# 01.net
KiCad netlist of a schematic drawn in Altium Designer
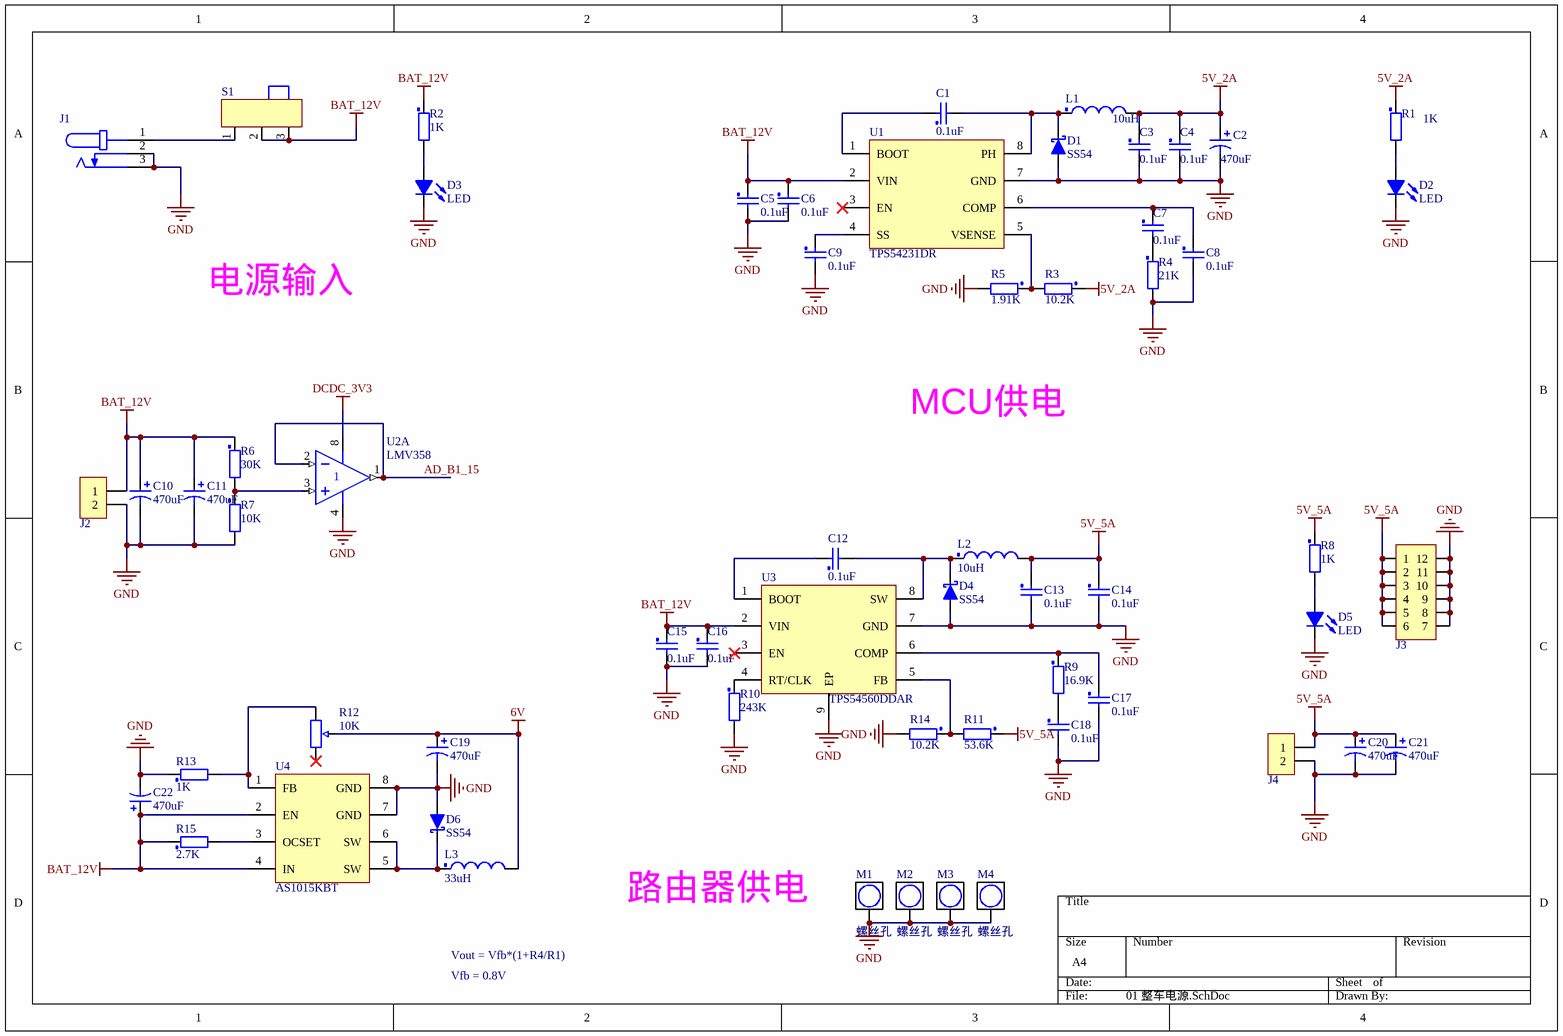
[diagram p0: 01 整车电源.SchDoc]

(export (version "E")
  (design (tool "Eeschema 10.0.6"))
  (components
    (comp (ref "C1")
      (value "0.1uF")
      (footprint "cap0603")
      (description "贴片电容")
      (fields (field (name "PUBLISHER") "Altium Limited"))
      (libsource (lib "元件库") (part "Cap"))
    )
    (comp (ref "C2")
      (value "470uF")
      (footprint "Cap8x10.5mm")
      (description "贴片电解电容 8*10.5mm")
      (fields (field (name "PUBLISHER") "Altium Limited"))
      (libsource (lib "元件库") (part "Cap Pol"))
    )
    (comp (ref "C3")
      (value "0.1uF")
      (footprint "cap0603")
      (description "贴片电容")
      (fields (field (name "PUBLISHER") "Altium Limited"))
      (libsource (lib "元件库") (part "Cap"))
    )
    (comp (ref "C4")
      (value "0.1uF")
      (footprint "cap0603")
      (description "贴片电容")
      (fields (field (name "PUBLISHER") "Altium Limited"))
      (libsource (lib "元件库") (part "Cap"))
    )
    (comp (ref "C5")
      (value "0.1uF")
      (footprint "cap0603")
      (description "贴片电容")
      (fields (field (name "PUBLISHER") "Altium Limited"))
      (libsource (lib "元件库") (part "Cap"))
    )
    (comp (ref "C6")
      (value "0.1uF")
      (footprint "cap0603")
      (description "贴片电容")
      (fields (field (name "PUBLISHER") "Altium Limited"))
      (libsource (lib "元件库") (part "Cap"))
    )
    (comp (ref "C7")
      (value "0.1uF")
      (footprint "cap0603")
      (description "贴片电容")
      (fields (field (name "PUBLISHER") "Altium Limited"))
      (libsource (lib "元件库") (part "Cap"))
    )
    (comp (ref "C8")
      (value "0.1uF")
      (footprint "cap0603")
      (description "贴片电容")
      (fields (field (name "PUBLISHER") "Altium Limited"))
      (libsource (lib "元件库") (part "Cap"))
    )
    (comp (ref "C9")
      (value "0.1uF")
      (footprint "cap0603")
      (description "贴片电容")
      (fields (field (name "PUBLISHER") "Altium Limited"))
      (libsource (lib "元件库") (part "Cap"))
    )
    (comp (ref "C10")
      (value "470uF")
      (footprint "Cap8x10.5mm")
      (description "贴片电解电容 8*10.5mm")
      (fields (field (name "PUBLISHER") "Altium Limited"))
      (libsource (lib "元件库") (part "Cap Pol"))
    )
    (comp (ref "C11")
      (value "470uF")
      (footprint "Cap8x10.5mm")
      (description "贴片电解电容 8*10.5mm")
      (fields (field (name "PUBLISHER") "Altium Limited"))
      (libsource (lib "元件库") (part "Cap Pol"))
    )
    (comp (ref "C12")
      (value "0.1uF")
      (footprint "cap0603")
      (description "贴片电容")
      (fields (field (name "PUBLISHER") "Altium Limited"))
      (libsource (lib "元件库") (part "Cap"))
    )
    (comp (ref "C13")
      (value "0.1uF")
      (footprint "cap0603")
      (description "贴片电容")
      (fields (field (name "PUBLISHER") "Altium Limited"))
      (libsource (lib "元件库") (part "Cap"))
    )
    (comp (ref "C14")
      (value "0.1uF")
      (footprint "cap0603")
      (description "贴片电容")
      (fields (field (name "PUBLISHER") "Altium Limited"))
      (libsource (lib "元件库") (part "Cap"))
    )
    (comp (ref "C15")
      (value "0.1uF")
      (footprint "cap0603")
      (description "贴片电容")
      (fields (field (name "PUBLISHER") "Altium Limited"))
      (libsource (lib "元件库") (part "Cap"))
    )
    (comp (ref "C16")
      (value "0.1uF")
      (footprint "cap0603")
      (description "贴片电容")
      (fields (field (name "PUBLISHER") "Altium Limited"))
      (libsource (lib "元件库") (part "Cap"))
    )
    (comp (ref "C17")
      (value "0.1uF")
      (footprint "cap0603")
      (description "贴片电容")
      (fields (field (name "PUBLISHER") "Altium Limited"))
      (libsource (lib "元件库") (part "Cap"))
    )
    (comp (ref "C18")
      (value "0.1uF")
      (footprint "cap0603")
      (description "贴片电容")
      (fields (field (name "PUBLISHER") "Altium Limited"))
      (libsource (lib "元件库") (part "Cap"))
    )
    (comp (ref "C19")
      (value "470uF")
      (footprint "Cap8x10.5mm")
      (description "贴片电解电容 8*10.5mm")
      (fields (field (name "PUBLISHER") "Altium Limited"))
      (libsource (lib "元件库") (part "Cap Pol"))
    )
    (comp (ref "C20")
      (value "470uF")
      (footprint "Cap8x10.5mm")
      (description "贴片电解电容 8*10.5mm")
      (fields (field (name "PUBLISHER") "Altium Limited"))
      (libsource (lib "元件库") (part "Cap Pol"))
    )
    (comp (ref "C21")
      (value "470uF")
      (footprint "Cap8x10.5mm")
      (description "贴片电解电容 8*10.5mm")
      (fields (field (name "PUBLISHER") "Altium Limited"))
      (libsource (lib "元件库") (part "Cap Pol"))
    )
    (comp (ref "C22")
      (value "470uF")
      (footprint "Cap8x10.5mm")
      (description "贴片电解电容 8*10.5mm")
      (fields (field (name "PUBLISHER") "Altium Limited"))
      (libsource (lib "元件库") (part "Cap Pol"))
    )
    (comp (ref "D1")
      (value "SS54")
      (footprint "SMA(DO-214AC)")
      (description "肖特基二极管")
      (fields (field (name "PUBLISHER") "Altium Limited"))
      (libsource (lib "元件库") (part "D Schottky"))
    )
    (comp (ref "D2")
      (value "LED")
      (footprint "LED")
      (description "贴片LED")
      (fields (field (name "PUBLISHER") "Altium Limited"))
      (libsource (lib "元件库") (part "LED"))
    )
    (comp (ref "D3")
      (value "LED")
      (footprint "LED")
      (description "贴片LED")
      (fields (field (name "PUBLISHER") "Altium Limited"))
      (libsource (lib "元件库") (part "LED"))
    )
    (comp (ref "D4")
      (value "SS54")
      (footprint "SMA(DO-214AC)")
      (description "肖特基二极管")
      (fields (field (name "PUBLISHER") "Altium Limited"))
      (libsource (lib "元件库") (part "D Schottky"))
    )
    (comp (ref "D5")
      (value "LED")
      (footprint "LED")
      (description "贴片LED")
      (fields (field (name "PUBLISHER") "Altium Limited"))
      (libsource (lib "元件库") (part "LED"))
    )
    (comp (ref "D6")
      (value "SS54")
      (footprint "SMA(DO-214AC)")
      (description "肖特基二极管")
      (fields (field (name "PUBLISHER") "Altium Limited"))
      (libsource (lib "元件库") (part "D Schottky"))
    )
    (comp (ref "J1")
      (value "DC输入插座")
      (footprint "DC_IN")
      (description "型号DC-005  外径5.5内径2.1 立创编号C136744")
      (libsource (lib "元件库") (part "DC输入插座"))
    )
    (comp (ref "J2")
      (value "接插件1")
      (footprint "5.08_2p")
      (description "5.08mm拔插式阶段端子，弯针")
      (fields (field (name "版权归属") "源创客"))
      (libsource (lib "元件库") (part "Header 2"))
    )
    (comp (ref "J3")
      (value "2x6")
      (footprint "2*8")
      (description "2.54mm公排针")
      (fields (field (name "版权归属") "源创客"))
      (libsource (lib "元件库") (part "Header 6x2"))
    )
    (comp (ref "J4")
      (value "接插件1")
      (footprint "5.08_2p")
      (description "5.08mm拔插式阶段端子，弯针")
      (fields (field (name "版权归属") "源创客"))
      (libsource (lib "元件库") (part "Header 2"))
    )
    (comp (ref "L1")
      (value "10uH")
      (footprint "CD43")
      (description "贴片功率电感")
      (fields (field (name "PUBLISHER") "Altium Limited"))
      (libsource (lib "元件库") (part "Inductor"))
    )
    (comp (ref "L2")
      (value "10uH")
      (footprint "CD43")
      (description "贴片功率电感")
      (fields (field (name "PUBLISHER") "Altium Limited"))
      (libsource (lib "元件库") (part "Inductor"))
    )
    (comp (ref "L3")
      (value "33uH")
      (footprint "CD43")
      (description "贴片功率电感")
      (fields (field (name "PUBLISHER") "Altium Limited"))
      (libsource (lib "元件库") (part "Inductor"))
    )
    (comp (ref "M1") (value "螺丝孔") (footprint "螺丝孔") (libsource (lib "元件库") (part "螺丝孔")))
    (comp (ref "M2") (value "螺丝孔") (footprint "螺丝孔") (libsource (lib "元件库") (part "螺丝孔")))
    (comp (ref "M3") (value "螺丝孔") (footprint "螺丝孔") (libsource (lib "元件库") (part "螺丝孔")))
    (comp (ref "M4") (value "螺丝孔") (footprint "螺丝孔") (libsource (lib "元件库") (part "螺丝孔")))
    (comp (ref "R1")
      (value "1K")
      (footprint "res0603")
      (description "贴片电阻")
      (fields (field (name "PUBLISHER") "Altium Limited"))
      (libsource (lib "元件库") (part "Res"))
    )
    (comp (ref "R2")
      (value "1K")
      (footprint "res0603")
      (description "贴片电阻")
      (fields (field (name "PUBLISHER") "Altium Limited"))
      (libsource (lib "元件库") (part "Res"))
    )
    (comp (ref "R3")
      (value "10.2K")
      (footprint "res0603")
      (description "贴片电阻")
      (fields (field (name "PUBLISHER") "Altium Limited"))
      (libsource (lib "") (part "Res_2"))
    )
    (comp (ref "R4")
      (value "21K")
      (footprint "res0603")
      (description "贴片电阻")
      (fields (field (name "PUBLISHER") "Altium Limited"))
      (libsource (lib "元件库") (part "Res"))
    )
    (comp (ref "R5")
      (value "1.91K")
      (footprint "res0603")
      (description "贴片电阻")
      (fields (field (name "PUBLISHER") "Altium Limited"))
      (libsource (lib "") (part "Res_2"))
    )
    (comp (ref "R6")
      (value "30K")
      (footprint "res0603")
      (description "贴片电阻")
      (fields (field (name "PUBLISHER") "Altium Limited"))
      (libsource (lib "元件库") (part "Res"))
    )
    (comp (ref "R7")
      (value "10K")
      (footprint "res0603")
      (description "贴片电阻")
      (fields (field (name "PUBLISHER") "Altium Limited"))
      (libsource (lib "元件库") (part "Res"))
    )
    (comp (ref "R8")
      (value "1K")
      (footprint "res0603")
      (description "贴片电阻")
      (fields (field (name "PUBLISHER") "Altium Limited"))
      (libsource (lib "元件库") (part "Res"))
    )
    (comp (ref "R9")
      (value "16.9K")
      (footprint "res0603")
      (description "贴片电阻")
      (fields (field (name "PUBLISHER") "Altium Limited"))
      (libsource (lib "元件库") (part "Res"))
    )
    (comp (ref "R10")
      (value "243K")
      (footprint "res0603")
      (description "贴片电阻")
      (fields (field (name "PUBLISHER") "Altium Limited"))
      (libsource (lib "元件库") (part "Res"))
    )
    (comp (ref "R11")
      (value "53.6K")
      (footprint "res0603")
      (description "贴片电阻")
      (fields (field (name "PUBLISHER") "Altium Limited"))
      (libsource (lib "") (part "Res_2"))
    )
    (comp (ref "R12")
      (value "10K")
      (footprint "3266W")
      (description "贴片电阻")
      (fields (field (name "PUBLISHER") "Altium Limited"))
      (libsource (lib "元件库") (part "Res Adj"))
    )
    (comp (ref "R13")
      (value "1K")
      (footprint "res0603")
      (description "贴片电阻")
      (fields (field (name "PUBLISHER") "Altium Limited"))
      (libsource (lib "") (part "Res_1"))
    )
    (comp (ref "R14")
      (value "10.2K")
      (footprint "res0603")
      (description "贴片电阻")
      (fields (field (name "PUBLISHER") "Altium Limited"))
      (libsource (lib "") (part "Res_2"))
    )
    (comp (ref "R15")
      (value "2.7K")
      (footprint "res0603")
      (description "贴片电阻")
      (fields (field (name "PUBLISHER") "Altium Limited"))
      (libsource (lib "") (part "Res_1"))
    )
    (comp (ref "S1")
      (value "小型扭子开关")
      (footprint "3p-switch")
      (description "三脚二挡 型号MTS102")
      (libsource (lib "元件库") (part "小型扭子开关"))
    )
    (comp (ref "U1")
      (value "TPS54231DR")
      (footprint "SOIC-8_150mil")
      (description "开关稳压芯片,3.5V~28V输入,2A输出")
      (libsource (lib "元件库") (part "TPS54231DR"))
    )
    (comp (ref "U2")
      (value "LMV358")
      (footprint "OPA2350")
      (description "运算放大器")
      (fields (field (name "PUBLISHER") "Altium Limited"))
      (libsource (lib "元件库") (part "LMV358"))
    )
    (comp (ref "U3")
      (value "TPS54560DDAR")
      (footprint "SOIC-8_EP_150mil")
      (description "开关稳压芯片,4.5V~60V输入,5A输出")
      (libsource (lib "元件库") (part "TPS54560DDAR"))
    )
    (comp (ref "U4")
      (value "AS1015KBT")
      (footprint "SOP18-AS1015")
      (description "开关稳压芯片")
      (libsource (lib "元件库") (part "AS1015KBT"))
    )
  )
  (nets
    (net (code "1") (name "/AD_B1_15") (class "Default")
      (node (ref "U2") (pin "1") (pinfunction "OUT_1") (pintype "output"))
      (node (ref "U2") (pin "2") (pinfunction "IN-_2") (pintype "input"))
    )
    (net (code "2") (name "5V_2A") (class "Default")
      (node (ref "C2") (pin "1") (pinfunction "1_1") (pintype "passive"))
      (node (ref "C3") (pin "1") (pinfunction "1_1") (pintype "passive"))
      (node (ref "C4") (pin "1") (pinfunction "1_1") (pintype "passive"))
      (node (ref "L1") (pin "2") (pinfunction "2_2") (pintype "passive"))
      (node (ref "R1") (pin "1") (pinfunction "1_1") (pintype "passive"))
      (node (ref "R3") (pin "1") (pinfunction "1_1") (pintype "passive"))
    )
    (net (code "3") (name "5V_5A") (class "Default")
      (node (ref "C13") (pin "1") (pinfunction "1_1") (pintype "passive"))
      (node (ref "C14") (pin "1") (pinfunction "1_1") (pintype "passive"))
      (node (ref "C20") (pin "1") (pinfunction "1_1") (pintype "passive"))
      (node (ref "C21") (pin "1") (pinfunction "1_1") (pintype "passive"))
      (node (ref "J3") (pin "1") (pinfunction "1_1") (pintype "passive"))
      (node (ref "J3") (pin "2") (pinfunction "2_2") (pintype "passive"))
      (node (ref "J3") (pin "3") (pinfunction "3_3") (pintype "passive"))
      (node (ref "J3") (pin "4") (pinfunction "4_4") (pintype "passive"))
      (node (ref "J3") (pin "5") (pinfunction "5_5") (pintype "passive"))
      (node (ref "J3") (pin "6") (pinfunction "6_6") (pintype "passive"))
      (node (ref "J4") (pin "1") (pinfunction "1_1") (pintype "passive"))
      (node (ref "L2") (pin "2") (pinfunction "2_2") (pintype "passive"))
      (node (ref "R11") (pin "1") (pinfunction "1_1") (pintype "passive"))
      (node (ref "R8") (pin "1") (pinfunction "1_1") (pintype "passive"))
    )
    (net (code "4") (name "6V") (class "Default")
      (node (ref "C19") (pin "1") (pinfunction "1_1") (pintype "passive"))
      (node (ref "L3") (pin "2") (pinfunction "2_2") (pintype "passive"))
      (node (ref "R12") (pin "2") (pinfunction "2_2") (pintype "passive"))
    )
    (net (code "5") (name "BAT_12V") (class "Default")
      (node (ref "C10") (pin "1") (pinfunction "1_1") (pintype "passive"))
      (node (ref "C11") (pin "1") (pinfunction "1_1") (pintype "passive"))
      (node (ref "C15") (pin "1") (pinfunction "1_1") (pintype "passive"))
      (node (ref "C16") (pin "1") (pinfunction "1_1") (pintype "passive"))
      (node (ref "C22") (pin "1") (pinfunction "1_1") (pintype "passive"))
      (node (ref "C5") (pin "1") (pinfunction "1_1") (pintype "passive"))
      (node (ref "C6") (pin "1") (pinfunction "1_1") (pintype "passive"))
      (node (ref "J2") (pin "1") (pinfunction "1_1") (pintype "passive"))
      (node (ref "R15") (pin "1") (pinfunction "1_1") (pintype "passive"))
      (node (ref "R2") (pin "1") (pinfunction "1_1") (pintype "passive"))
      (node (ref "R6") (pin "1") (pinfunction "1_1") (pintype "passive"))
      (node (ref "S1") (pin "2") (pintype "passive"))
      (node (ref "S1") (pin "3") (pintype "passive"))
      (node (ref "U1") (pin "2") (pinfunction "VIN_2") (pintype "passive"))
      (node (ref "U3") (pin "2") (pinfunction "VIN_2") (pintype "passive"))
      (node (ref "U4") (pin "2") (pinfunction "EN_2") (pintype "passive"))
      (node (ref "U4") (pin "4") (pinfunction "IN_4") (pintype "passive"))
    )
    (net (code "6") (name "DCDC_3V3") (class "Default")
      (node (ref "U2") (pin "8") (pinfunction "V+_8") (pintype "power_in"))
    )
    (net (code "7") (name "GND") (class "Default")
      (node (ref "C10") (pin "2") (pinfunction "2_2") (pintype "passive"))
      (node (ref "C11") (pin "2") (pinfunction "2_2") (pintype "passive"))
      (node (ref "C13") (pin "2") (pinfunction "2_2") (pintype "passive"))
      (node (ref "C14") (pin "2") (pinfunction "2_2") (pintype "passive"))
      (node (ref "C15") (pin "2") (pinfunction "2_2") (pintype "passive"))
      (node (ref "C16") (pin "2") (pinfunction "2_2") (pintype "passive"))
      (node (ref "C17") (pin "2") (pinfunction "2_2") (pintype "passive"))
      (node (ref "C18") (pin "2") (pinfunction "2_2") (pintype "passive"))
      (node (ref "C19") (pin "2") (pinfunction "2_2") (pintype "passive"))
      (node (ref "C2") (pin "2") (pinfunction "2_2") (pintype "passive"))
      (node (ref "C20") (pin "2") (pinfunction "2_2") (pintype "passive"))
      (node (ref "C21") (pin "2") (pinfunction "2_2") (pintype "passive"))
      (node (ref "C22") (pin "2") (pinfunction "2_2") (pintype "passive"))
      (node (ref "C3") (pin "2") (pinfunction "2_2") (pintype "passive"))
      (node (ref "C4") (pin "2") (pinfunction "2_2") (pintype "passive"))
      (node (ref "C5") (pin "2") (pinfunction "2_2") (pintype "passive"))
      (node (ref "C6") (pin "2") (pinfunction "2_2") (pintype "passive"))
      (node (ref "C8") (pin "2") (pinfunction "2_2") (pintype "passive"))
      (node (ref "C9") (pin "2") (pinfunction "2_2") (pintype "passive"))
      (node (ref "D1") (pin "1") (pinfunction "A_1") (pintype "passive"))
      (node (ref "D2") (pin "2") (pinfunction "K_2") (pintype "passive"))
      (node (ref "D3") (pin "2") (pinfunction "K_2") (pintype "passive"))
      (node (ref "D4") (pin "1") (pinfunction "A_1") (pintype "passive"))
      (node (ref "D5") (pin "2") (pinfunction "K_2") (pintype "passive"))
      (node (ref "D6") (pin "1") (pinfunction "A_1") (pintype "passive"))
      (node (ref "J1") (pin "2") (pinfunction "GND_2") (pintype "passive"))
      (node (ref "J1") (pin "3") (pinfunction "GND_3") (pintype "passive"))
      (node (ref "J2") (pin "2") (pinfunction "2_2") (pintype "passive"))
      (node (ref "J3") (pin "10") (pinfunction "10_10") (pintype "passive"))
      (node (ref "J3") (pin "11") (pinfunction "11_11") (pintype "passive"))
      (node (ref "J3") (pin "12") (pinfunction "12_12") (pintype "passive"))
      (node (ref "J3") (pin "7") (pinfunction "7_7") (pintype "passive"))
      (node (ref "J3") (pin "8") (pinfunction "8_8") (pintype "passive"))
      (node (ref "J3") (pin "9") (pinfunction "9_9") (pintype "passive"))
      (node (ref "J4") (pin "2") (pinfunction "2_2") (pintype "passive"))
      (node (ref "M1") (pin "0") (pinfunction "0_0") (pintype "passive"))
      (node (ref "M2") (pin "0") (pinfunction "0_0") (pintype "passive"))
      (node (ref "M3") (pin "0") (pinfunction "0_0") (pintype "passive"))
      (node (ref "M4") (pin "0") (pinfunction "0_0") (pintype "passive"))
      (node (ref "R10") (pin "2") (pinfunction "2_2") (pintype "passive"))
      (node (ref "R13") (pin "1") (pinfunction "1_1") (pintype "passive"))
      (node (ref "R14") (pin "2") (pinfunction "2_2") (pintype "passive"))
      (node (ref "R4") (pin "2") (pinfunction "2_2") (pintype "passive"))
      (node (ref "R5") (pin "2") (pinfunction "2_2") (pintype "passive"))
      (node (ref "R7") (pin "2") (pinfunction "2_2") (pintype "passive"))
      (node (ref "U1") (pin "7") (pinfunction "GND_7") (pintype "passive"))
      (node (ref "U2") (pin "4") (pinfunction "V-_4") (pintype "power_in"))
      (node (ref "U3") (pin "7") (pinfunction "GND_7") (pintype "passive"))
      (node (ref "U3") (pin "9") (pinfunction "EP_9") (pintype "passive"))
      (node (ref "U4") (pin "7") (pinfunction "GND_7") (pintype "passive"))
      (node (ref "U4") (pin "8") (pinfunction "GND_8") (pintype "passive"))
    )
    (net (code "8") (name "Net-(C7-Pad2)") (class "Default")
      (node (ref "C7") (pin "2") (pinfunction "2_2") (pintype "passive"))
      (node (ref "R4") (pin "1") (pinfunction "1_1") (pintype "passive"))
    )
    (net (code "9") (name "Net-(C18-Pad1)") (class "Default")
      (node (ref "C18") (pin "1") (pinfunction "1_1") (pintype "passive"))
      (node (ref "R9") (pin "2") (pinfunction "2_2") (pintype "passive"))
    )
    (net (code "10") (name "Net-(D1-K)") (class "Default")
      (node (ref "C1") (pin "2") (pinfunction "2_2") (pintype "passive"))
      (node (ref "D1") (pin "2") (pinfunction "K_2") (pintype "passive"))
      (node (ref "L1") (pin "1") (pinfunction "1_1") (pintype "passive"))
      (node (ref "U1") (pin "8") (pinfunction "PH_8") (pintype "passive"))
    )
    (net (code "11") (name "Net-(D2-A)") (class "Default")
      (node (ref "D2") (pin "1") (pinfunction "A_1") (pintype "passive"))
      (node (ref "R1") (pin "2") (pinfunction "2_2") (pintype "passive"))
    )
    (net (code "12") (name "Net-(D3-A)") (class "Default")
      (node (ref "D3") (pin "1") (pinfunction "A_1") (pintype "passive"))
      (node (ref "R2") (pin "2") (pinfunction "2_2") (pintype "passive"))
    )
    (net (code "13") (name "Net-(D4-K)") (class "Default")
      (node (ref "C12") (pin "2") (pinfunction "2_2") (pintype "passive"))
      (node (ref "D4") (pin "2") (pinfunction "K_2") (pintype "passive"))
      (node (ref "L2") (pin "1") (pinfunction "1_1") (pintype "passive"))
      (node (ref "U3") (pin "8") (pinfunction "SW_8") (pintype "passive"))
    )
    (net (code "14") (name "Net-(D5-A)") (class "Default")
      (node (ref "D5") (pin "1") (pinfunction "A_1") (pintype "passive"))
      (node (ref "R8") (pin "2") (pinfunction "2_2") (pintype "passive"))
    )
    (net (code "15") (name "Net-(D6-K)") (class "Default")
      (node (ref "D6") (pin "2") (pinfunction "K_2") (pintype "passive"))
      (node (ref "L3") (pin "1") (pinfunction "1_1") (pintype "passive"))
      (node (ref "U4") (pin "5") (pinfunction "SW_5") (pintype "passive"))
      (node (ref "U4") (pin "6") (pinfunction "SW_6") (pintype "passive"))
    )
    (net (code "16") (name "Net-(J1-VCC)") (class "Default")
      (node (ref "J1") (pin "1") (pinfunction "VCC_1") (pintype "passive"))
      (node (ref "S1") (pin "1") (pintype "passive"))
    )
    (net (code "17") (name "Net-(U1-BOOT)") (class "Default")
      (node (ref "C1") (pin "1") (pinfunction "1_1") (pintype "passive"))
      (node (ref "U1") (pin "1") (pinfunction "BOOT_1") (pintype "passive"))
    )
    (net (code "18") (name "Net-(U1-COMP)") (class "Default")
      (node (ref "C7") (pin "1") (pinfunction "1_1") (pintype "passive"))
      (node (ref "C8") (pin "1") (pinfunction "1_1") (pintype "passive"))
      (node (ref "U1") (pin "6") (pinfunction "COMP_6") (pintype "passive"))
    )
    (net (code "19") (name "Net-(U1-SS)") (class "Default")
      (node (ref "C9") (pin "1") (pinfunction "1_1") (pintype "passive"))
      (node (ref "U1") (pin "4") (pinfunction "SS_4") (pintype "passive"))
    )
    (net (code "20") (name "Net-(U1-VSENSE)") (class "Default")
      (node (ref "R3") (pin "2") (pinfunction "2_2") (pintype "passive"))
      (node (ref "R5") (pin "1") (pinfunction "1_1") (pintype "passive"))
      (node (ref "U1") (pin "5") (pinfunction "VSENSE_5") (pintype "passive"))
    )
    (net (code "21") (name "Net-(U2A-IN+)") (class "Default")
      (node (ref "R6") (pin "2") (pinfunction "2_2") (pintype "passive"))
      (node (ref "R7") (pin "1") (pinfunction "1_1") (pintype "passive"))
      (node (ref "U2") (pin "3") (pinfunction "IN+_3") (pintype "input"))
    )
    (net (code "22") (name "Net-(U3-BOOT)") (class "Default")
      (node (ref "C12") (pin "1") (pinfunction "1_1") (pintype "passive"))
      (node (ref "U3") (pin "1") (pinfunction "BOOT_1") (pintype "passive"))
    )
    (net (code "23") (name "Net-(U3-COMP)") (class "Default")
      (node (ref "C17") (pin "1") (pinfunction "1_1") (pintype "passive"))
      (node (ref "R9") (pin "1") (pinfunction "1_1") (pintype "passive"))
      (node (ref "U3") (pin "6") (pinfunction "COMP_6") (pintype "passive"))
    )
    (net (code "24") (name "Net-(U3-FB)") (class "Default")
      (node (ref "R11") (pin "2") (pinfunction "2_2") (pintype "passive"))
      (node (ref "R14") (pin "1") (pinfunction "1_1") (pintype "passive"))
      (node (ref "U3") (pin "5") (pinfunction "FB_5") (pintype "passive"))
    )
    (net (code "25") (name "Net-(U3-RT{slash}CLK)") (class "Default")
      (node (ref "R10") (pin "1") (pinfunction "1_1") (pintype "passive"))
      (node (ref "U3") (pin "4") (pinfunction "RT/CLK_4") (pintype "passive"))
    )
    (net (code "26") (name "Net-(U4-FB)") (class "Default")
      (node (ref "R12") (pin "3") (pinfunction "3_3") (pintype "passive"))
      (node (ref "R13") (pin "2") (pinfunction "2_2") (pintype "passive"))
      (node (ref "U4") (pin "1") (pinfunction "FB_1") (pintype "passive"))
    )
    (net (code "27") (name "Net-(U4-OCSET)") (class "Default")
      (node (ref "R15") (pin "2") (pinfunction "2_2") (pintype "passive"))
      (node (ref "U4") (pin "3") (pinfunction "OCSET_3") (pintype "passive"))
    )
    (net (code "28") (name "unconnected-(R12-Pad1)") (class "Default")
      (node (ref "R12") (pin "1") (pinfunction "1_1") (pintype "passive+no_connect"))
    )
    (net (code "29") (name "unconnected-(U1-EN-Pad3)") (class "Default")
      (node (ref "U1") (pin "3") (pinfunction "EN_3") (pintype "passive+no_connect"))
    )
    (net (code "30") (name "unconnected-(U3-EN-Pad3)") (class "Default")
      (node (ref "U3") (pin "3") (pinfunction "EN_3") (pintype "passive+no_connect"))
    )
  )
)
